# uZed_breakout.net
KiCad netlist of a schematic drawn in Altium Designer
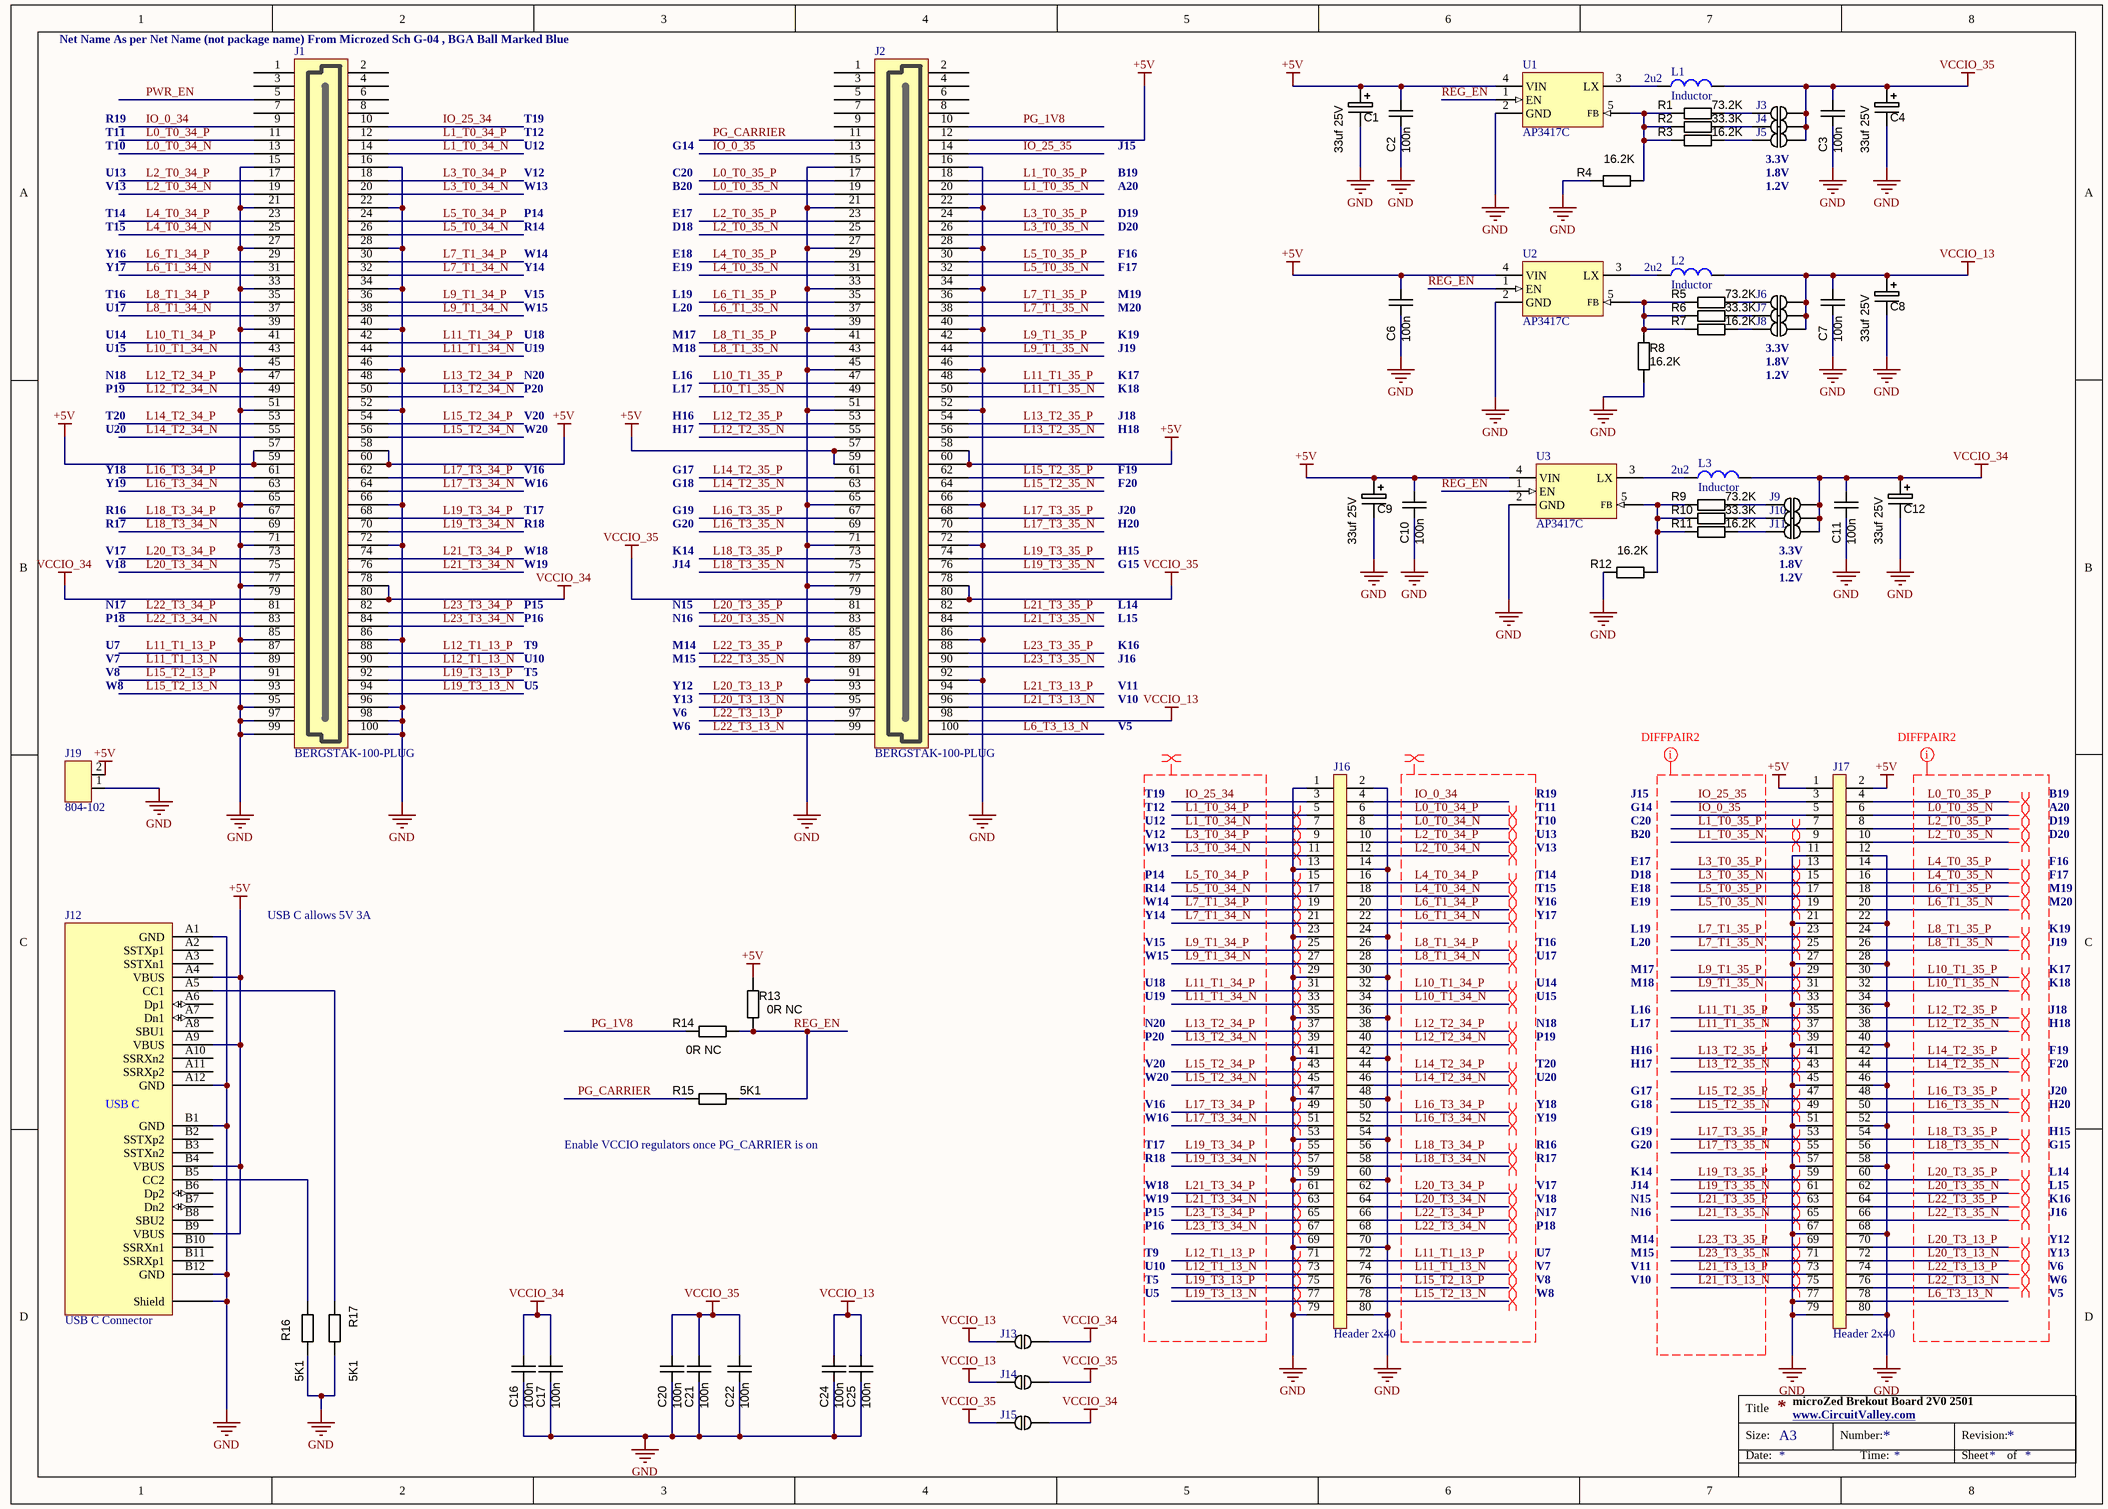
[diagram p0: uZed_breakout.SchDoc]

(export (version "E")
  (design (tool "Eeschema 10.0.6"))
  (components
    (comp (ref "C1")
      (value "33uf 25V")
      (footprint "CAPMP7343X310N")
      (description "Capacitor SMD Tant 330uF 20% 6V3 2917")
      (fields
        (field (name "TOLERANCE") "±20%")
        (field (name "MANUFACTURER PART NUMBER") "T520D337M006ATE015")
      )
      (libsource (lib "PBL - Capacitors") (part "CAPT_330u_2917_6V3"))
    )
    (comp (ref "C2")
      (value "100n")
      (footprint "CAPC1608N")
      (description "Capacitor SMD Cer 10pF 5% 50V NP0 0603")
      (fields (field (name "TOLERANCE") "±5%") (field (name "PART") "C0603X104K5RAC"))
      (libsource (lib "PBL - Capacitors") (part "CAPC_10p_0603_NP0_1%_50V"))
    )
    (comp (ref "C3")
      (value "100n")
      (footprint "CAPC1608N")
      (description "Capacitor SMD Cer 10pF 5% 50V NP0 0603")
      (fields (field (name "TOLERANCE") "±5%") (field (name "PART") "C0603X104K5RAC"))
      (libsource (lib "PBL - Capacitors") (part "CAPC_10p_0603_NP0_1%_50V"))
    )
    (comp (ref "C4")
      (value "33uf 25V")
      (footprint "CAPMP7343X310N")
      (description "Capacitor SMD Tant 330uF 20% 6V3 2917")
      (fields
        (field (name "TOLERANCE") "±20%")
        (field (name "MANUFACTURER PART NUMBER") "T520D337M006ATE015")
      )
      (libsource (lib "PBL - Capacitors") (part "CAPT_330u_2917_6V3"))
    )
    (comp (ref "C6")
      (value "100n")
      (footprint "CAPC1608N")
      (description "Capacitor SMD Cer 10pF 5% 50V NP0 0603")
      (fields (field (name "TOLERANCE") "±5%") (field (name "PART") "C0603X104K5RAC"))
      (libsource (lib "PBL - Capacitors") (part "CAPC_10p_0603_NP0_1%_50V"))
    )
    (comp (ref "C7")
      (value "100n")
      (footprint "CAPC1608N")
      (description "Capacitor SMD Cer 10pF 5% 50V NP0 0603")
      (fields (field (name "TOLERANCE") "±5%") (field (name "PART") "C0603X104K5RAC"))
      (libsource (lib "PBL - Capacitors") (part "CAPC_10p_0603_NP0_1%_50V"))
    )
    (comp (ref "C8")
      (value "33uf 25V")
      (footprint "CAPMP7343X310N")
      (description "Capacitor SMD Tant 330uF 20% 6V3 2917")
      (fields
        (field (name "TOLERANCE") "±20%")
        (field (name "MANUFACTURER PART NUMBER") "T520D337M006ATE015")
      )
      (libsource (lib "PBL - Capacitors") (part "CAPT_330u_2917_6V3"))
    )
    (comp (ref "C9")
      (value "33uf 25V")
      (footprint "CAPMP7343X310N")
      (description "Capacitor SMD Tant 330uF 20% 6V3 2917")
      (fields
        (field (name "TOLERANCE") "±20%")
        (field (name "MANUFACTURER PART NUMBER") "T520D337M006ATE015")
      )
      (libsource (lib "PBL - Capacitors") (part "CAPT_330u_2917_6V3"))
    )
    (comp (ref "C10")
      (value "100n")
      (footprint "CAPC1608N")
      (description "Capacitor SMD Cer 10pF 5% 50V NP0 0603")
      (fields (field (name "TOLERANCE") "±5%") (field (name "PART") "C0603X104K5RAC"))
      (libsource (lib "PBL - Capacitors") (part "CAPC_10p_0603_NP0_1%_50V"))
    )
    (comp (ref "C11")
      (value "100n")
      (footprint "CAPC1608N")
      (description "Capacitor SMD Cer 10pF 5% 50V NP0 0603")
      (fields (field (name "TOLERANCE") "±5%") (field (name "PART") "C0603X104K5RAC"))
      (libsource (lib "PBL - Capacitors") (part "CAPC_10p_0603_NP0_1%_50V"))
    )
    (comp (ref "C12")
      (value "33uf 25V")
      (footprint "CAPMP7343X310N")
      (description "Capacitor SMD Tant 330uF 20% 6V3 2917")
      (fields
        (field (name "TOLERANCE") "±20%")
        (field (name "MANUFACTURER PART NUMBER") "T520D337M006ATE015")
      )
      (libsource (lib "PBL - Capacitors") (part "CAPT_330u_2917_6V3"))
    )
    (comp (ref "C16")
      (value "100n")
      (footprint "CAPC1608N")
      (description "Capacitor SMD Cer 10pF 5% 50V NP0 0603")
      (fields (field (name "TOLERANCE") "±5%") (field (name "PART") "C0603X104K5RAC"))
      (libsource (lib "PBL - Capacitors") (part "CAPC_10p_0603_NP0_1%_50V"))
    )
    (comp (ref "C17")
      (value "100n")
      (footprint "CAPC1608N")
      (description "Capacitor SMD Cer 10pF 5% 50V NP0 0603")
      (fields (field (name "TOLERANCE") "±5%") (field (name "PART") "C0603X104K5RAC"))
      (libsource (lib "PBL - Capacitors") (part "CAPC_10p_0603_NP0_1%_50V"))
    )
    (comp (ref "C20")
      (value "100n")
      (footprint "CAPC1608N")
      (description "Capacitor SMD Cer 10pF 5% 50V NP0 0603")
      (fields (field (name "TOLERANCE") "±5%") (field (name "PART") "C0603X104K5RAC"))
      (libsource (lib "PBL - Capacitors") (part "CAPC_10p_0603_NP0_1%_50V"))
    )
    (comp (ref "C21")
      (value "100n")
      (footprint "CAPC1608N")
      (description "Capacitor SMD Cer 10pF 5% 50V NP0 0603")
      (fields (field (name "TOLERANCE") "±5%") (field (name "PART") "C0603X104K5RAC"))
      (libsource (lib "PBL - Capacitors") (part "CAPC_10p_0603_NP0_1%_50V"))
    )
    (comp (ref "C22")
      (value "100n")
      (footprint "CAPC1608N")
      (description "Capacitor SMD Cer 10pF 5% 50V NP0 0603")
      (fields (field (name "TOLERANCE") "±5%") (field (name "PART") "C0603X104K5RAC"))
      (libsource (lib "PBL - Capacitors") (part "CAPC_10p_0603_NP0_1%_50V"))
    )
    (comp (ref "C24")
      (value "100n")
      (footprint "CAPC1608N")
      (description "Capacitor SMD Cer 10pF 5% 50V NP0 0603")
      (fields (field (name "TOLERANCE") "±5%") (field (name "PART") "C0603X104K5RAC"))
      (libsource (lib "PBL - Capacitors") (part "CAPC_10p_0603_NP0_1%_50V"))
    )
    (comp (ref "C25")
      (value "100n")
      (footprint "CAPC1608N")
      (description "Capacitor SMD Cer 10pF 5% 50V NP0 0603")
      (fields (field (name "TOLERANCE") "±5%") (field (name "PART") "C0603X104K5RAC"))
      (libsource (lib "PBL - Capacitors") (part "CAPC_10p_0603_NP0_1%_50V"))
    )
    (comp (ref "J1")
      (value "BERGSTAK-100-PLUG")
      (footprint "61083-101400LF")
      (libsource (lib "cvlib") (part "BERGSTAK-100-PLUG"))
    )
    (comp (ref "J2")
      (value "BERGSTAK-100-PLUG")
      (footprint "61083-101400LF")
      (libsource (lib "cvlib") (part "BERGSTAK-100-PLUG"))
    )
    (comp (ref "J3")
      (value "SMD Jumper")
      (footprint "SMD_Jumper")
      (libsource (lib "cvlib") (part "SMD_Jumper"))
    )
    (comp (ref "J4")
      (value "SMD Jumper Bridged")
      (footprint "SMD_Jumper_bridge")
      (description "SMD Jumper")
      (libsource (lib "cvlib") (part "SMD_Jumper_Bridged"))
    )
    (comp (ref "J5")
      (value "SMD Jumper")
      (footprint "SMD_Jumper")
      (libsource (lib "cvlib") (part "SMD_Jumper"))
    )
    (comp (ref "J6")
      (value "SMD Jumper")
      (footprint "SMD_Jumper")
      (libsource (lib "cvlib") (part "SMD_Jumper"))
    )
    (comp (ref "J7")
      (value "SMD Jumper Bridged")
      (footprint "SMD_Jumper_bridge")
      (description "SMD Jumper")
      (libsource (lib "cvlib") (part "SMD_Jumper_Bridged"))
    )
    (comp (ref "J8")
      (value "SMD Jumper")
      (footprint "SMD_Jumper")
      (libsource (lib "cvlib") (part "SMD_Jumper"))
    )
    (comp (ref "J9")
      (value "SMD Jumper")
      (footprint "SMD_Jumper")
      (libsource (lib "cvlib") (part "SMD_Jumper"))
    )
    (comp (ref "J10")
      (value "SMD Jumper Bridged")
      (footprint "SMD_Jumper_bridge")
      (description "SMD Jumper")
      (libsource (lib "cvlib") (part "SMD_Jumper_Bridged"))
    )
    (comp (ref "J11")
      (value "SMD Jumper")
      (footprint "SMD_Jumper")
      (libsource (lib "cvlib") (part "SMD_Jumper"))
    )
    (comp (ref "J12")
      (value "USB C Connector")
      (footprint "UT11113-11602-7H")
      (description "USB C connector")
      (libsource (lib "cvlib") (part "USB_C"))
    )
    (comp (ref "J13")
      (value "SMD Jumper")
      (footprint "SMD_Jumper")
      (libsource (lib "cvlib") (part "SMD_Jumper"))
    )
    (comp (ref "J14")
      (value "SMD Jumper")
      (footprint "SMD_Jumper")
      (libsource (lib "cvlib") (part "SMD_Jumper"))
    )
    (comp (ref "J15")
      (value "SMD Jumper")
      (footprint "SMD_Jumper")
      (libsource (lib "cvlib") (part "SMD_Jumper"))
    )
    (comp (ref "J16")
      (value "Header 2x40")
      (footprint "Header_2x40")
      (libsource (lib "cvlib") (part "Header_2x40"))
    )
    (comp (ref "J17")
      (value "Header 2x40")
      (footprint "Header_2x40")
      (libsource (lib "cvlib") (part "Header_2x40"))
    )
    (comp (ref "J19") (value "804-102") (footprint "804-102") (libsource (lib "cvlib") (part "804-102")))
    (comp (ref "L1")
      (value "Inductor")
      (footprint "SFE4018A-2R2M-F-HF")
      (fields (field (name "ALTIUM_VALUE") "2u2"))
      (libsource (lib "cvlib") (part "inductor_smd"))
    )
    (comp (ref "L2")
      (value "Inductor")
      (footprint "SFE4018A-2R2M-F-HF")
      (fields (field (name "ALTIUM_VALUE") "2u2"))
      (libsource (lib "cvlib") (part "inductor_smd"))
    )
    (comp (ref "L3")
      (value "Inductor")
      (footprint "SFE4018A-2R2M-F-HF")
      (fields (field (name "ALTIUM_VALUE") "2u2"))
      (libsource (lib "cvlib") (part "inductor_smd"))
    )
    (comp (ref "R1")
      (value "73.2K")
      (footprint "RESC1608N_ZERO")
      (description "Resistor SMD chip 0.0 Ohm 0.1W 0603")
      (fields (field (name "TOLERANCE") "±5%") (field (name "Comment") "Thick Film"))
      (libsource (lib "PBL - Resistors") (part "RES_0R_0603"))
    )
    (comp (ref "R2")
      (value "33.3K")
      (footprint "RESC1608N_ZERO")
      (description "Resistor SMD chip 0.0 Ohm 0.1W 0603")
      (fields (field (name "TOLERANCE") "±5%") (field (name "Comment") "Thick Film"))
      (libsource (lib "PBL - Resistors") (part "RES_0R_0603"))
    )
    (comp (ref "R3")
      (value "16.2K")
      (footprint "RESC1608N_ZERO")
      (description "Resistor SMD chip 0.0 Ohm 0.1W 0603")
      (fields (field (name "TOLERANCE") "±5%") (field (name "Comment") "Thick Film"))
      (libsource (lib "PBL - Resistors") (part "RES_0R_0603"))
    )
    (comp (ref "R4")
      (value "16.2K")
      (footprint "RESC1608N_ZERO")
      (description "Resistor SMD chip 0.0 Ohm 0.1W 0603")
      (fields (field (name "TOLERANCE") "±5%") (field (name "Comment") "Thick Film"))
      (libsource (lib "PBL - Resistors") (part "RES_0R_0603"))
    )
    (comp (ref "R5")
      (value "73.2K")
      (footprint "RESC1608N_ZERO")
      (description "Resistor SMD chip 0.0 Ohm 0.1W 0603")
      (fields (field (name "TOLERANCE") "±5%") (field (name "Comment") "Thick Film"))
      (libsource (lib "") (part "RES_0R_0603_3"))
    )
    (comp (ref "R6")
      (value "33.3K")
      (footprint "RESC1608N_ZERO")
      (description "Resistor SMD chip 0.0 Ohm 0.1W 0603")
      (fields (field (name "TOLERANCE") "±5%") (field (name "Comment") "Thick Film"))
      (libsource (lib "") (part "RES_0R_0603_3"))
    )
    (comp (ref "R7")
      (value "16.2K")
      (footprint "RESC1608N_ZERO")
      (description "Resistor SMD chip 0.0 Ohm 0.1W 0603")
      (fields (field (name "TOLERANCE") "±5%") (field (name "Comment") "Thick Film"))
      (libsource (lib "") (part "RES_0R_0603_3"))
    )
    (comp (ref "R8")
      (value "16.2K")
      (footprint "RESC1608N_ZERO")
      (description "Resistor SMD chip 0.0 Ohm 0.1W 0603")
      (fields (field (name "TOLERANCE") "±5%") (field (name "Comment") "Thick Film"))
      (libsource (lib "") (part "RES_0R_0603_1"))
    )
    (comp (ref "R9")
      (value "73.2K")
      (footprint "RESC1608N_ZERO")
      (description "Resistor SMD chip 0.0 Ohm 0.1W 0603")
      (fields (field (name "TOLERANCE") "±5%") (field (name "Comment") "Thick Film"))
      (libsource (lib "PBL - Resistors") (part "RES_0R_0603"))
    )
    (comp (ref "R10")
      (value "33.3K")
      (footprint "RESC1608N_ZERO")
      (description "Resistor SMD chip 0.0 Ohm 0.1W 0603")
      (fields (field (name "TOLERANCE") "±5%") (field (name "Comment") "Thick Film"))
      (libsource (lib "PBL - Resistors") (part "RES_0R_0603"))
    )
    (comp (ref "R11")
      (value "16.2K")
      (footprint "RESC1608N_ZERO")
      (description "Resistor SMD chip 0.0 Ohm 0.1W 0603")
      (fields (field (name "TOLERANCE") "±5%") (field (name "Comment") "Thick Film"))
      (libsource (lib "PBL - Resistors") (part "RES_0R_0603"))
    )
    (comp (ref "R12")
      (value "16.2K")
      (footprint "RESC1608N_ZERO")
      (description "Resistor SMD chip 0.0 Ohm 0.1W 0603")
      (fields (field (name "TOLERANCE") "±5%") (field (name "Comment") "Thick Film"))
      (libsource (lib "PBL - Resistors") (part "RES_0R_0603"))
    )
    (comp (ref "R13")
      (value "0R NC")
      (footprint "RESC1608N_ZERO")
      (description "Resistor SMD chip 0.0 Ohm 0.1W 0603")
      (fields (field (name "TOLERANCE") "±5%") (field (name "Comment") "Thick Film"))
      (libsource (lib "") (part "RES_0R_0603_2"))
    )
    (comp (ref "R14")
      (value "0R NC")
      (footprint "RESC1608N_ZERO")
      (description "Resistor SMD chip 0.0 Ohm 0.1W 0603")
      (fields (field (name "TOLERANCE") "±5%") (field (name "Comment") "Thick Film"))
      (libsource (lib "PBL - Resistors") (part "RES_0R_0603"))
    )
    (comp (ref "R15")
      (value "5K1")
      (footprint "RESC1608N_ZERO")
      (description "Resistor SMD chip 0.0 Ohm 0.1W 0603")
      (fields (field (name "TOLERANCE") "±5%") (field (name "Comment") "Thick Film"))
      (libsource (lib "PBL - Resistors") (part "RES_0R_0603"))
    )
    (comp (ref "R16")
      (value "5K1")
      (footprint "RESC1608N_ZERO")
      (description "Resistor SMD chip 0.0 Ohm 0.1W 0603")
      (fields (field (name "TOLERANCE") "±5%") (field (name "Comment") "Thick Film"))
      (libsource (lib "") (part "RES_0R_0603_2"))
    )
    (comp (ref "R17")
      (value "5K1")
      (footprint "RESC1608N_ZERO")
      (description "Resistor SMD chip 0.0 Ohm 0.1W 0603")
      (fields (field (name "TOLERANCE") "±5%") (field (name "Comment") "Thick Film"))
      (libsource (lib "") (part "RES_0R_0603_2"))
    )
    (comp (ref "U1") (value "AP3417C") (footprint "SOT23-5") (libsource (lib "cvlib") (part "AP3417C")))
    (comp (ref "U2") (value "AP3417C") (footprint "SOT23-5") (libsource (lib "cvlib") (part "AP3417C")))
    (comp (ref "U3") (value "AP3417C") (footprint "SOT23-5") (libsource (lib "cvlib") (part "AP3417C")))
  )
  (nets
    (net (code "1") (name "+5V") (class "Default")
      (node (ref "C1") (pin "1") (pintype "passive"))
      (node (ref "C10") (pin "2") (pintype "passive"))
      (node (ref "C2") (pin "2") (pintype "passive"))
      (node (ref "C6") (pin "2") (pintype "passive"))
      (node (ref "C9") (pin "1") (pintype "passive"))
      (node (ref "J1") (pin "57") (pinfunction "57_57") (pintype "passive"))
      (node (ref "J1") (pin "58") (pinfunction "58_58") (pintype "passive"))
      (node (ref "J1") (pin "59") (pinfunction "59_59") (pintype "passive"))
      (node (ref "J1") (pin "60") (pinfunction "60_60") (pintype "passive"))
      (node (ref "J12") (pin "A4") (pinfunction "VBUS_A4") (pintype "power_in"))
      (node (ref "J12") (pin "A9") (pinfunction "VBUS_A9") (pintype "power_in"))
      (node (ref "J12") (pin "B4") (pinfunction "VBUS_B4") (pintype "power_in"))
      (node (ref "J12") (pin "B9") (pinfunction "VBUS_B9") (pintype "power_in"))
      (node (ref "J17") (pin "1") (pinfunction "1_1") (pintype "passive"))
      (node (ref "J17") (pin "2") (pinfunction "2_2") (pintype "passive"))
      (node (ref "J19") (pin "2") (pinfunction "PW_2") (pintype "passive"))
      (node (ref "J2") (pin "12") (pinfunction "12_12") (pintype "passive"))
      (node (ref "J2") (pin "57") (pinfunction "57_57") (pintype "passive"))
      (node (ref "J2") (pin "58") (pinfunction "58_58") (pintype "passive"))
      (node (ref "J2") (pin "59") (pinfunction "59_59") (pintype "passive"))
      (node (ref "J2") (pin "60") (pinfunction "60_60") (pintype "passive"))
      (node (ref "R13") (pin "1") (pinfunction "1_1") (pintype "passive"))
      (node (ref "U1") (pin "4") (pinfunction "VIN_4") (pintype "power_in"))
      (node (ref "U2") (pin "4") (pinfunction "VIN_4") (pintype "power_in"))
      (node (ref "U3") (pin "4") (pinfunction "VIN_4") (pintype "power_in"))
    )
    (net (code "2") (name "/IO_0_34") (class "Default")
      (node (ref "J1") (pin "9") (pinfunction "9_9") (pintype "passive"))
      (node (ref "J16") (pin "4") (pinfunction "4_4") (pintype "passive"))
    )
    (net (code "3") (name "/IO_0_35") (class "Default")
      (node (ref "J17") (pin "5") (pinfunction "5_5") (pintype "passive"))
      (node (ref "J2") (pin "13") (pinfunction "13_13") (pintype "passive"))
    )
    (net (code "4") (name "/IO_25_34") (class "Default")
      (node (ref "J1") (pin "10") (pinfunction "10_10") (pintype "passive"))
      (node (ref "J16") (pin "3") (pinfunction "3_3") (pintype "passive"))
    )
    (net (code "5") (name "/IO_25_35") (class "Default")
      (node (ref "J17") (pin "3") (pinfunction "3_3") (pintype "passive"))
      (node (ref "J2") (pin "14") (pinfunction "14_14") (pintype "passive"))
    )
    (net (code "6") (name "/L0_T0_34_N") (class "Default")
      (node (ref "J1") (pin "13") (pinfunction "13_13") (pintype "passive"))
      (node (ref "J16") (pin "8") (pinfunction "8_8") (pintype "passive"))
    )
    (net (code "7") (name "/L0_T0_34_P") (class "Default")
      (node (ref "J1") (pin "11") (pinfunction "11_11") (pintype "passive"))
      (node (ref "J16") (pin "6") (pinfunction "6_6") (pintype "passive"))
    )
    (net (code "8") (name "/L0_T0_35_N") (class "Default")
      (node (ref "J17") (pin "6") (pinfunction "6_6") (pintype "passive"))
      (node (ref "J2") (pin "19") (pinfunction "19_19") (pintype "passive"))
    )
    (net (code "9") (name "/L0_T0_35_P") (class "Default")
      (node (ref "J17") (pin "4") (pinfunction "4_4") (pintype "passive"))
      (node (ref "J2") (pin "17") (pinfunction "17_17") (pintype "passive"))
    )
    (net (code "10") (name "/L1_T0_34_N") (class "Default")
      (node (ref "J1") (pin "14") (pinfunction "14_14") (pintype "passive"))
      (node (ref "J16") (pin "7") (pinfunction "7_7") (pintype "passive"))
    )
    (net (code "11") (name "/L1_T0_34_P") (class "Default")
      (node (ref "J1") (pin "12") (pinfunction "12_12") (pintype "passive"))
      (node (ref "J16") (pin "5") (pinfunction "5_5") (pintype "passive"))
    )
    (net (code "12") (name "/L1_T0_35_N") (class "Default")
      (node (ref "J17") (pin "9") (pinfunction "9_9") (pintype "passive"))
      (node (ref "J2") (pin "20") (pinfunction "20_20") (pintype "passive"))
    )
    (net (code "13") (name "/L1_T0_35_P") (class "Default")
      (node (ref "J17") (pin "7") (pinfunction "7_7") (pintype "passive"))
      (node (ref "J2") (pin "18") (pinfunction "18_18") (pintype "passive"))
    )
    (net (code "14") (name "/L2_T0_34_N") (class "Default")
      (node (ref "J1") (pin "19") (pinfunction "19_19") (pintype "passive"))
      (node (ref "J16") (pin "12") (pinfunction "12_12") (pintype "passive"))
    )
    (net (code "15") (name "/L2_T0_34_P") (class "Default")
      (node (ref "J1") (pin "17") (pinfunction "17_17") (pintype "passive"))
      (node (ref "J16") (pin "10") (pinfunction "10_10") (pintype "passive"))
    )
    (net (code "16") (name "/L2_T0_35_N") (class "Default")
      (node (ref "J17") (pin "10") (pinfunction "10_10") (pintype "passive"))
      (node (ref "J2") (pin "25") (pinfunction "25_25") (pintype "passive"))
    )
    (net (code "17") (name "/L2_T0_35_P") (class "Default")
      (node (ref "J17") (pin "8") (pinfunction "8_8") (pintype "passive"))
      (node (ref "J2") (pin "23") (pinfunction "23_23") (pintype "passive"))
    )
    (net (code "18") (name "/L3_T0_34_N") (class "Default")
      (node (ref "J1") (pin "20") (pinfunction "20_20") (pintype "passive"))
      (node (ref "J16") (pin "11") (pinfunction "11_11") (pintype "passive"))
    )
    (net (code "19") (name "/L3_T0_34_P") (class "Default")
      (node (ref "J1") (pin "18") (pinfunction "18_18") (pintype "passive"))
      (node (ref "J16") (pin "9") (pinfunction "9_9") (pintype "passive"))
    )
    (net (code "20") (name "/L3_T0_35_N") (class "Default")
      (node (ref "J17") (pin "15") (pinfunction "15_15") (pintype "passive"))
      (node (ref "J2") (pin "26") (pinfunction "26_26") (pintype "passive"))
    )
    (net (code "21") (name "/L3_T0_35_P") (class "Default")
      (node (ref "J17") (pin "13") (pinfunction "13_13") (pintype "passive"))
      (node (ref "J2") (pin "24") (pinfunction "24_24") (pintype "passive"))
    )
    (net (code "22") (name "/L4_T0_34_N") (class "Default")
      (node (ref "J1") (pin "25") (pinfunction "25_25") (pintype "passive"))
      (node (ref "J16") (pin "18") (pinfunction "18_18") (pintype "passive"))
    )
    (net (code "23") (name "/L4_T0_34_P") (class "Default")
      (node (ref "J1") (pin "23") (pinfunction "23_23") (pintype "passive"))
      (node (ref "J16") (pin "16") (pinfunction "16_16") (pintype "passive"))
    )
    (net (code "24") (name "/L4_T0_35_N") (class "Default")
      (node (ref "J17") (pin "16") (pinfunction "16_16") (pintype "passive"))
      (node (ref "J2") (pin "31") (pinfunction "31_31") (pintype "passive"))
    )
    (net (code "25") (name "/L4_T0_35_P") (class "Default")
      (node (ref "J17") (pin "14") (pinfunction "14_14") (pintype "passive"))
      (node (ref "J2") (pin "29") (pinfunction "29_29") (pintype "passive"))
    )
    (net (code "26") (name "/L5_T0_34_N") (class "Default")
      (node (ref "J1") (pin "26") (pinfunction "26_26") (pintype "passive"))
      (node (ref "J16") (pin "17") (pinfunction "17_17") (pintype "passive"))
    )
    (net (code "27") (name "/L5_T0_34_P") (class "Default")
      (node (ref "J1") (pin "24") (pinfunction "24_24") (pintype "passive"))
      (node (ref "J16") (pin "15") (pinfunction "15_15") (pintype "passive"))
    )
    (net (code "28") (name "/L5_T0_35_N") (class "Default")
      (node (ref "J17") (pin "19") (pinfunction "19_19") (pintype "passive"))
      (node (ref "J2") (pin "32") (pinfunction "32_32") (pintype "passive"))
    )
    (net (code "29") (name "/L5_T0_35_P") (class "Default")
      (node (ref "J17") (pin "17") (pinfunction "17_17") (pintype "passive"))
      (node (ref "J2") (pin "30") (pinfunction "30_30") (pintype "passive"))
    )
    (net (code "30") (name "/L6_T1_34_N") (class "Default")
      (node (ref "J1") (pin "31") (pinfunction "31_31") (pintype "passive"))
      (node (ref "J16") (pin "22") (pinfunction "22_22") (pintype "passive"))
    )
    (net (code "31") (name "/L6_T1_34_P") (class "Default")
      (node (ref "J1") (pin "29") (pinfunction "29_29") (pintype "passive"))
      (node (ref "J16") (pin "20") (pinfunction "20_20") (pintype "passive"))
    )
    (net (code "32") (name "/L6_T1_35_N") (class "Default")
      (node (ref "J17") (pin "20") (pinfunction "20_20") (pintype "passive"))
      (node (ref "J2") (pin "37") (pinfunction "37_37") (pintype "passive"))
    )
    (net (code "33") (name "/L6_T1_35_P") (class "Default")
      (node (ref "J17") (pin "18") (pinfunction "18_18") (pintype "passive"))
      (node (ref "J2") (pin "35") (pinfunction "35_35") (pintype "passive"))
    )
    (net (code "34") (name "/L6_T3_13_N") (class "Default")
      (node (ref "J17") (pin "78") (pinfunction "78_78") (pintype "passive"))
      (node (ref "J2") (pin "100") (pinfunction "100_100") (pintype "passive"))
    )
    (net (code "35") (name "/L7_T1_34_N") (class "Default")
      (node (ref "J1") (pin "32") (pinfunction "32_32") (pintype "passive"))
      (node (ref "J16") (pin "21") (pinfunction "21_21") (pintype "passive"))
    )
    (net (code "36") (name "/L7_T1_34_P") (class "Default")
      (node (ref "J1") (pin "30") (pinfunction "30_30") (pintype "passive"))
      (node (ref "J16") (pin "19") (pinfunction "19_19") (pintype "passive"))
    )
    (net (code "37") (name "/L7_T1_35_N") (class "Default")
      (node (ref "J17") (pin "25") (pinfunction "25_25") (pintype "passive"))
      (node (ref "J2") (pin "38") (pinfunction "38_38") (pintype "passive"))
    )
    (net (code "38") (name "/L7_T1_35_P") (class "Default")
      (node (ref "J17") (pin "23") (pinfunction "23_23") (pintype "passive"))
      (node (ref "J2") (pin "36") (pinfunction "36_36") (pintype "passive"))
    )
    (net (code "39") (name "/L8_T1_34_N") (class "Default")
      (node (ref "J1") (pin "37") (pinfunction "37_37") (pintype "passive"))
      (node (ref "J16") (pin "28") (pinfunction "28_28") (pintype "passive"))
    )
    (net (code "40") (name "/L8_T1_34_P") (class "Default")
      (node (ref "J1") (pin "35") (pinfunction "35_35") (pintype "passive"))
      (node (ref "J16") (pin "26") (pinfunction "26_26") (pintype "passive"))
    )
    (net (code "41") (name "/L8_T1_35_N") (class "Default")
      (node (ref "J17") (pin "26") (pinfunction "26_26") (pintype "passive"))
      (node (ref "J2") (pin "43") (pinfunction "43_43") (pintype "passive"))
    )
    (net (code "42") (name "/L8_T1_35_P") (class "Default")
      (node (ref "J17") (pin "24") (pinfunction "24_24") (pintype "passive"))
      (node (ref "J2") (pin "41") (pinfunction "41_41") (pintype "passive"))
    )
    (net (code "43") (name "/L9_T1_34_N") (class "Default")
      (node (ref "J1") (pin "38") (pinfunction "38_38") (pintype "passive"))
      (node (ref "J16") (pin "27") (pinfunction "27_27") (pintype "passive"))
    )
    (net (code "44") (name "/L9_T1_34_P") (class "Default")
      (node (ref "J1") (pin "36") (pinfunction "36_36") (pintype "passive"))
      (node (ref "J16") (pin "25") (pinfunction "25_25") (pintype "passive"))
    )
    (net (code "45") (name "/L9_T1_35_N") (class "Default")
      (node (ref "J17") (pin "31") (pinfunction "31_31") (pintype "passive"))
      (node (ref "J2") (pin "44") (pinfunction "44_44") (pintype "passive"))
    )
    (net (code "46") (name "/L9_T1_35_P") (class "Default")
      (node (ref "J17") (pin "29") (pinfunction "29_29") (pintype "passive"))
      (node (ref "J2") (pin "42") (pinfunction "42_42") (pintype "passive"))
    )
    (net (code "47") (name "/L10_T1_34_N") (class "Default")
      (node (ref "J1") (pin "43") (pinfunction "43_43") (pintype "passive"))
      (node (ref "J16") (pin "34") (pinfunction "34_34") (pintype "passive"))
    )
    (net (code "48") (name "/L10_T1_34_P") (class "Default")
      (node (ref "J1") (pin "41") (pinfunction "41_41") (pintype "passive"))
      (node (ref "J16") (pin "32") (pinfunction "32_32") (pintype "passive"))
    )
    (net (code "49") (name "/L10_T1_35_N") (class "Default")
      (node (ref "J17") (pin "32") (pinfunction "32_32") (pintype "passive"))
      (node (ref "J2") (pin "49") (pinfunction "49_49") (pintype "passive"))
    )
    (net (code "50") (name "/L10_T1_35_P") (class "Default")
      (node (ref "J17") (pin "30") (pinfunction "30_30") (pintype "passive"))
      (node (ref "J2") (pin "47") (pinfunction "47_47") (pintype "passive"))
    )
    (net (code "51") (name "/L11_T1_13_N") (class "Default")
      (node (ref "J1") (pin "89") (pinfunction "89_89") (pintype "passive"))
      (node (ref "J16") (pin "74") (pinfunction "74_74") (pintype "passive"))
    )
    (net (code "52") (name "/L11_T1_13_P") (class "Default")
      (node (ref "J1") (pin "87") (pinfunction "87_87") (pintype "passive"))
      (node (ref "J16") (pin "72") (pinfunction "72_72") (pintype "passive"))
    )
    (net (code "53") (name "/L11_T1_34_N") (class "Default")
      (node (ref "J1") (pin "44") (pinfunction "44_44") (pintype "passive"))
      (node (ref "J16") (pin "33") (pinfunction "33_33") (pintype "passive"))
    )
    (net (code "54") (name "/L11_T1_34_P") (class "Default")
      (node (ref "J1") (pin "42") (pinfunction "42_42") (pintype "passive"))
      (node (ref "J16") (pin "31") (pinfunction "31_31") (pintype "passive"))
    )
    (net (code "55") (name "/L11_T1_35_N") (class "Default")
      (node (ref "J17") (pin "37") (pinfunction "37_37") (pintype "passive"))
      (node (ref "J2") (pin "50") (pinfunction "50_50") (pintype "passive"))
    )
    (net (code "56") (name "/L11_T1_35_P") (class "Default")
      (node (ref "J17") (pin "35") (pinfunction "35_35") (pintype "passive"))
      (node (ref "J2") (pin "48") (pinfunction "48_48") (pintype "passive"))
    )
    (net (code "57") (name "/L12_T1_13_N") (class "Default")
      (node (ref "J1") (pin "90") (pinfunction "90_90") (pintype "passive"))
      (node (ref "J16") (pin "73") (pinfunction "73_73") (pintype "passive"))
    )
    (net (code "58") (name "/L12_T1_13_P") (class "Default")
      (node (ref "J1") (pin "88") (pinfunction "88_88") (pintype "passive"))
      (node (ref "J16") (pin "71") (pinfunction "71_71") (pintype "passive"))
    )
    (net (code "59") (name "/L12_T2_34_N") (class "Default")
      (node (ref "J1") (pin "49") (pinfunction "49_49") (pintype "passive"))
      (node (ref "J16") (pin "40") (pinfunction "40_40") (pintype "passive"))
    )
    (net (code "60") (name "/L12_T2_34_P") (class "Default")
      (node (ref "J1") (pin "47") (pinfunction "47_47") (pintype "passive"))
      (node (ref "J16") (pin "38") (pinfunction "38_38") (pintype "passive"))
    )
    (net (code "61") (name "/L12_T2_35_N") (class "Default")
      (node (ref "J17") (pin "38") (pinfunction "38_38") (pintype "passive"))
      (node (ref "J2") (pin "55") (pinfunction "55_55") (pintype "passive"))
    )
    (net (code "62") (name "/L12_T2_35_P") (class "Default")
      (node (ref "J17") (pin "36") (pinfunction "36_36") (pintype "passive"))
      (node (ref "J2") (pin "53") (pinfunction "53_53") (pintype "passive"))
    )
    (net (code "63") (name "/L13_T2_34_N") (class "Default")
      (node (ref "J1") (pin "50") (pinfunction "50_50") (pintype "passive"))
      (node (ref "J16") (pin "39") (pinfunction "39_39") (pintype "passive"))
    )
    (net (code "64") (name "/L13_T2_34_P") (class "Default")
      (node (ref "J1") (pin "48") (pinfunction "48_48") (pintype "passive"))
      (node (ref "J16") (pin "37") (pinfunction "37_37") (pintype "passive"))
    )
    (net (code "65") (name "/L13_T2_35_N") (class "Default")
      (node (ref "J17") (pin "43") (pinfunction "43_43") (pintype "passive"))
      (node (ref "J2") (pin "56") (pinfunction "56_56") (pintype "passive"))
    )
    (net (code "66") (name "/L13_T2_35_P") (class "Default")
      (node (ref "J17") (pin "41") (pinfunction "41_41") (pintype "passive"))
      (node (ref "J2") (pin "54") (pinfunction "54_54") (pintype "passive"))
    )
    (net (code "67") (name "/L14_T2_34_N") (class "Default")
      (node (ref "J1") (pin "55") (pinfunction "55_55") (pintype "passive"))
      (node (ref "J16") (pin "46") (pinfunction "46_46") (pintype "passive"))
    )
    (net (code "68") (name "/L14_T2_34_P") (class "Default")
      (node (ref "J1") (pin "53") (pinfunction "53_53") (pintype "passive"))
      (node (ref "J16") (pin "44") (pinfunction "44_44") (pintype "passive"))
    )
    (net (code "69") (name "/L14_T2_35_N") (class "Default")
      (node (ref "J17") (pin "44") (pinfunction "44_44") (pintype "passive"))
      (node (ref "J2") (pin "63") (pinfunction "63_63") (pintype "passive"))
    )
    (net (code "70") (name "/L14_T2_35_P") (class "Default")
      (node (ref "J17") (pin "42") (pinfunction "42_42") (pintype "passive"))
      (node (ref "J2") (pin "61") (pinfunction "61_61") (pintype "passive"))
    )
    (net (code "71") (name "/L15_T2_13_N") (class "Default")
      (node (ref "J1") (pin "93") (pinfunction "93_93") (pintype "passive"))
      (node (ref "J16") (pin "78") (pinfunction "78_78") (pintype "passive"))
    )
    (net (code "72") (name "/L15_T2_13_P") (class "Default")
      (node (ref "J1") (pin "91") (pinfunction "91_91") (pintype "passive"))
      (node (ref "J16") (pin "76") (pinfunction "76_76") (pintype "passive"))
    )
    (net (code "73") (name "/L15_T2_34_N") (class "Default")
      (node (ref "J1") (pin "56") (pinfunction "56_56") (pintype "passive"))
      (node (ref "J16") (pin "45") (pinfunction "45_45") (pintype "passive"))
    )
    (net (code "74") (name "/L15_T2_34_P") (class "Default")
      (node (ref "J1") (pin "54") (pinfunction "54_54") (pintype "passive"))
      (node (ref "J16") (pin "43") (pinfunction "43_43") (pintype "passive"))
    )
    (net (code "75") (name "/L15_T2_35_N") (class "Default")
      (node (ref "J17") (pin "49") (pinfunction "49_49") (pintype "passive"))
      (node (ref "J2") (pin "64") (pinfunction "64_64") (pintype "passive"))
    )
    (net (code "76") (name "/L15_T2_35_P") (class "Default")
      (node (ref "J17") (pin "47") (pinfunction "47_47") (pintype "passive"))
      (node (ref "J2") (pin "62") (pinfunction "62_62") (pintype "passive"))
    )
    (net (code "77") (name "/L16_T3_34_N") (class "Default")
      (node (ref "J1") (pin "63") (pinfunction "63_63") (pintype "passive"))
      (node (ref "J16") (pin "52") (pinfunction "52_52") (pintype "passive"))
    )
    (net (code "78") (name "/L16_T3_34_P") (class "Default")
      (node (ref "J1") (pin "61") (pinfunction "61_61") (pintype "passive"))
      (node (ref "J16") (pin "50") (pinfunction "50_50") (pintype "passive"))
    )
    (net (code "79") (name "/L16_T3_35_N") (class "Default")
      (node (ref "J17") (pin "50") (pinfunction "50_50") (pintype "passive"))
      (node (ref "J2") (pin "69") (pinfunction "69_69") (pintype "passive"))
    )
    (net (code "80") (name "/L16_T3_35_P") (class "Default")
      (node (ref "J17") (pin "48") (pinfunction "48_48") (pintype "passive"))
      (node (ref "J2") (pin "67") (pinfunction "67_67") (pintype "passive"))
    )
    (net (code "81") (name "/L17_T3_34_N") (class "Default")
      (node (ref "J1") (pin "64") (pinfunction "64_64") (pintype "passive"))
      (node (ref "J16") (pin "51") (pinfunction "51_51") (pintype "passive"))
    )
    (net (code "82") (name "/L17_T3_34_P") (class "Default")
      (node (ref "J1") (pin "62") (pinfunction "62_62") (pintype "passive"))
      (node (ref "J16") (pin "49") (pinfunction "49_49") (pintype "passive"))
    )
    (net (code "83") (name "/L17_T3_35_N") (class "Default")
      (node (ref "J17") (pin "55") (pinfunction "55_55") (pintype "passive"))
      (node (ref "J2") (pin "70") (pinfunction "70_70") (pintype "passive"))
    )
    (net (code "84") (name "/L17_T3_35_P") (class "Default")
      (node (ref "J17") (pin "53") (pinfunction "53_53") (pintype "passive"))
      (node (ref "J2") (pin "68") (pinfunction "68_68") (pintype "passive"))
    )
    (net (code "85") (name "/L18_T3_34_N") (class "Default")
      (node (ref "J1") (pin "69") (pinfunction "69_69") (pintype "passive"))
      (node (ref "J16") (pin "58") (pinfunction "58_58") (pintype "passive"))
    )
    (net (code "86") (name "/L18_T3_34_P") (class "Default")
      (node (ref "J1") (pin "67") (pinfunction "67_67") (pintype "passive"))
      (node (ref "J16") (pin "56") (pinfunction "56_56") (pintype "passive"))
    )
    (net (code "87") (name "/L18_T3_35_N") (class "Default")
      (node (ref "J17") (pin "56") (pinfunction "56_56") (pintype "passive"))
      (node (ref "J2") (pin "75") (pinfunction "75_75") (pintype "passive"))
    )
    (net (code "88") (name "/L18_T3_35_P") (class "Default")
      (node (ref "J17") (pin "54") (pinfunction "54_54") (pintype "passive"))
      (node (ref "J2") (pin "73") (pinfunction "73_73") (pintype "passive"))
    )
    (net (code "89") (name "/L19_T3_13_N") (class "Default")
      (node (ref "J1") (pin "94") (pinfunction "94_94") (pintype "passive"))
      (node (ref "J16") (pin "77") (pinfunction "77_77") (pintype "passive"))
    )
    (net (code "90") (name "/L19_T3_13_P") (class "Default")
      (node (ref "J1") (pin "92") (pinfunction "92_92") (pintype "passive"))
      (node (ref "J16") (pin "75") (pinfunction "75_75") (pintype "passive"))
    )
    (net (code "91") (name "/L19_T3_34_N") (class "Default")
      (node (ref "J1") (pin "70") (pinfunction "70_70") (pintype "passive"))
      (node (ref "J16") (pin "57") (pinfunction "57_57") (pintype "passive"))
    )
    (net (code "92") (name "/L19_T3_34_P") (class "Default")
      (node (ref "J1") (pin "68") (pinfunction "68_68") (pintype "passive"))
      (node (ref "J16") (pin "55") (pinfunction "55_55") (pintype "passive"))
    )
    (net (code "93") (name "/L19_T3_35_N") (class "Default")
      (node (ref "J17") (pin "61") (pinfunction "61_61") (pintype "passive"))
      (node (ref "J2") (pin "76") (pinfunction "76_76") (pintype "passive"))
    )
    (net (code "94") (name "/L19_T3_35_P") (class "Default")
      (node (ref "J17") (pin "59") (pinfunction "59_59") (pintype "passive"))
      (node (ref "J2") (pin "74") (pinfunction "74_74") (pintype "passive"))
    )
    (net (code "95") (name "/L20_T3_13_N") (class "Default")
      (node (ref "J17") (pin "72") (pinfunction "72_72") (pintype "passive"))
      (node (ref "J2") (pin "95") (pinfunction "95_95") (pintype "passive"))
    )
    (net (code "96") (name "/L20_T3_13_P") (class "Default")
      (node (ref "J17") (pin "70") (pinfunction "70_70") (pintype "passive"))
      (node (ref "J2") (pin "93") (pinfunction "93_93") (pintype "passive"))
    )
    (net (code "97") (name "/L20_T3_34_N") (class "Default")
      (node (ref "J1") (pin "75") (pinfunction "75_75") (pintype "passive"))
      (node (ref "J16") (pin "64") (pinfunction "64_64") (pintype "passive"))
    )
    (net (code "98") (name "/L20_T3_34_P") (class "Default")
      (node (ref "J1") (pin "73") (pinfunction "73_73") (pintype "passive"))
      (node (ref "J16") (pin "62") (pinfunction "62_62") (pintype "passive"))
    )
    (net (code "99") (name "/L20_T3_35_N") (class "Default")
      (node (ref "J17") (pin "62") (pinfunction "62_62") (pintype "passive"))
      (node (ref "J2") (pin "83") (pinfunction "83_83") (pintype "passive"))
    )
    (net (code "100") (name "/L20_T3_35_P") (class "Default")
      (node (ref "J17") (pin "60") (pinfunction "60_60") (pintype "passive"))
      (node (ref "J2") (pin "81") (pinfunction "81_81") (pintype "passive"))
    )
    (net (code "101") (name "/L21_T3_13_N") (class "Default")
      (node (ref "J17") (pin "75") (pinfunction "75_75") (pintype "passive"))
      (node (ref "J2") (pin "96") (pinfunction "96_96") (pintype "passive"))
    )
    (net (code "102") (name "/L21_T3_13_P") (class "Default")
      (node (ref "J17") (pin "73") (pinfunction "73_73") (pintype "passive"))
      (node (ref "J2") (pin "94") (pinfunction "94_94") (pintype "passive"))
    )
    (net (code "103") (name "/L21_T3_34_N") (class "Default")
      (node (ref "J1") (pin "76") (pinfunction "76_76") (pintype "passive"))
      (node (ref "J16") (pin "63") (pinfunction "63_63") (pintype "passive"))
    )
    (net (code "104") (name "/L21_T3_34_P") (class "Default")
      (node (ref "J1") (pin "74") (pinfunction "74_74") (pintype "passive"))
      (node (ref "J16") (pin "61") (pinfunction "61_61") (pintype "passive"))
    )
    (net (code "105") (name "/L21_T3_35_N") (class "Default")
      (node (ref "J17") (pin "65") (pinfunction "65_65") (pintype "passive"))
      (node (ref "J2") (pin "84") (pinfunction "84_84") (pintype "passive"))
    )
    (net (code "106") (name "/L21_T3_35_P") (class "Default")
      (node (ref "J17") (pin "63") (pinfunction "63_63") (pintype "passive"))
      (node (ref "J2") (pin "82") (pinfunction "82_82") (pintype "passive"))
    )
    (net (code "107") (name "/L22_T3_13_N") (class "Default")
      (node (ref "J17") (pin "76") (pinfunction "76_76") (pintype "passive"))
      (node (ref "J2") (pin "99") (pinfunction "99_99") (pintype "passive"))
    )
    (net (code "108") (name "/L22_T3_13_P") (class "Default")
      (node (ref "J17") (pin "74") (pinfunction "74_74") (pintype "passive"))
      (node (ref "J2") (pin "97") (pinfunction "97_97") (pintype "passive"))
    )
    (net (code "109") (name "/L22_T3_34_N") (class "Default")
      (node (ref "J1") (pin "83") (pinfunction "83_83") (pintype "passive"))
      (node (ref "J16") (pin "68") (pinfunction "68_68") (pintype "passive"))
    )
    (net (code "110") (name "/L22_T3_34_P") (class "Default")
      (node (ref "J1") (pin "81") (pinfunction "81_81") (pintype "passive"))
      (node (ref "J16") (pin "66") (pinfunction "66_66") (pintype "passive"))
    )
    (net (code "111") (name "/L22_T3_35_N") (class "Default")
      (node (ref "J17") (pin "66") (pinfunction "66_66") (pintype "passive"))
      (node (ref "J2") (pin "89") (pinfunction "89_89") (pintype "passive"))
    )
    (net (code "112") (name "/L22_T3_35_P") (class "Default")
      (node (ref "J17") (pin "64") (pinfunction "64_64") (pintype "passive"))
      (node (ref "J2") (pin "87") (pinfunction "87_87") (pintype "passive"))
    )
    (net (code "113") (name "/L23_T3_34_N") (class "Default")
      (node (ref "J1") (pin "84") (pinfunction "84_84") (pintype "passive"))
      (node (ref "J16") (pin "67") (pinfunction "67_67") (pintype "passive"))
    )
    (net (code "114") (name "/L23_T3_34_P") (class "Default")
      (node (ref "J1") (pin "82") (pinfunction "82_82") (pintype "passive"))
      (node (ref "J16") (pin "65") (pinfunction "65_65") (pintype "passive"))
    )
    (net (code "115") (name "/L23_T3_35_N") (class "Default")
      (node (ref "J17") (pin "71") (pinfunction "71_71") (pintype "passive"))
      (node (ref "J2") (pin "90") (pinfunction "90_90") (pintype "passive"))
    )
    (net (code "116") (name "/L23_T3_35_P") (class "Default")
      (node (ref "J17") (pin "69") (pinfunction "69_69") (pintype "passive"))
      (node (ref "J2") (pin "88") (pinfunction "88_88") (pintype "passive"))
    )
    (net (code "117") (name "/PG_1V8") (class "Default")
      (node (ref "J2") (pin "10") (pinfunction "10_10") (pintype "passive"))
      (node (ref "R14") (pin "2") (pinfunction "2_2") (pintype "passive"))
    )
    (net (code "118") (name "/PG_CARRIER") (class "Default")
      (node (ref "J2") (pin "11") (pinfunction "11_11") (pintype "passive"))
      (node (ref "R15") (pin "2") (pinfunction "2_2") (pintype "passive"))
    )
    (net (code "119") (name "/PWR_EN") (class "Default")
      (node (ref "J1") (pin "5") (pinfunction "5_5") (pintype "passive"))
    )
    (net (code "120") (name "/REG_EN") (class "Default")
      (node (ref "R13") (pin "2") (pinfunction "2_2") (pintype "passive"))
      (node (ref "R14") (pin "1") (pinfunction "1_1") (pintype "passive"))
      (node (ref "R15") (pin "1") (pinfunction "1_1") (pintype "passive"))
      (node (ref "U1") (pin "1") (pinfunction "EN_1") (pintype "input"))
      (node (ref "U2") (pin "1") (pinfunction "EN_1") (pintype "input"))
      (node (ref "U3") (pin "1") (pinfunction "EN_1") (pintype "input"))
    )
    (net (code "121") (name "GND") (class "Default")
      (node (ref "C1") (pin "2") (pintype "passive"))
      (node (ref "C10") (pin "1") (pintype "passive"))
      (node (ref "C11") (pin "1") (pintype "passive"))
      (node (ref "C12") (pin "2") (pintype "passive"))
      (node (ref "C16") (pin "1") (pintype "passive"))
      (node (ref "C17") (pin "1") (pintype "passive"))
      (node (ref "C2") (pin "1") (pintype "passive"))
      (node (ref "C20") (pin "1") (pintype "passive"))
      (node (ref "C21") (pin "1") (pintype "passive"))
      (node (ref "C22") (pin "1") (pintype "passive"))
      (node (ref "C24") (pin "1") (pintype "passive"))
      (node (ref "C25") (pin "1") (pintype "passive"))
      (node (ref "C3") (pin "1") (pintype "passive"))
      (node (ref "C4") (pin "2") (pintype "passive"))
      (node (ref "C6") (pin "1") (pintype "passive"))
      (node (ref "C7") (pin "1") (pintype "passive"))
      (node (ref "C8") (pin "2") (pintype "passive"))
      (node (ref "C9") (pin "2") (pintype "passive"))
      (node (ref "J1") (pin "100") (pinfunction "100_100") (pintype "passive"))
      (node (ref "J1") (pin "15") (pinfunction "15_15") (pintype "passive"))
      (node (ref "J1") (pin "16") (pinfunction "16_16") (pintype "passive"))
      (node (ref "J1") (pin "21") (pinfunction "21_21") (pintype "passive"))
      (node (ref "J1") (pin "22") (pinfunction "22_22") (pintype "passive"))
      (node (ref "J1") (pin "27") (pinfunction "27_27") (pintype "passive"))
      (node (ref "J1") (pin "28") (pinfunction "28_28") (pintype "passive"))
      (node (ref "J1") (pin "33") (pinfunction "33_33") (pintype "passive"))
      (node (ref "J1") (pin "34") (pinfunction "34_34") (pintype "passive"))
      (node (ref "J1") (pin "39") (pinfunction "39_39") (pintype "passive"))
      (node (ref "J1") (pin "40") (pinfunction "40_40") (pintype "passive"))
      (node (ref "J1") (pin "45") (pinfunction "45_45") (pintype "passive"))
      (node (ref "J1") (pin "46") (pinfunction "46_46") (pintype "passive"))
      (node (ref "J1") (pin "51") (pinfunction "51_51") (pintype "passive"))
      (node (ref "J1") (pin "52") (pinfunction "52_52") (pintype "passive"))
      (node (ref "J1") (pin "65") (pinfunction "65_65") (pintype "passive"))
      (node (ref "J1") (pin "66") (pinfunction "66_66") (pintype "passive"))
      (node (ref "J1") (pin "71") (pinfunction "71_71") (pintype "passive"))
      (node (ref "J1") (pin "72") (pinfunction "72_72") (pintype "passive"))
      (node (ref "J1") (pin "77") (pinfunction "77_77") (pintype "passive"))
      (node (ref "J1") (pin "85") (pinfunction "85_85") (pintype "passive"))
      (node (ref "J1") (pin "86") (pinfunction "86_86") (pintype "passive"))
      (node (ref "J1") (pin "95") (pinfunction "95_95") (pintype "passive"))
      (node (ref "J1") (pin "96") (pinfunction "96_96") (pintype "passive"))
      (node (ref "J1") (pin "97") (pinfunction "97_97") (pintype "passive"))
      (node (ref "J1") (pin "98") (pinfunction "98_98") (pintype "passive"))
      (node (ref "J1") (pin "99") (pinfunction "99_99") (pintype "passive"))
      (node (ref "J12") (pin "0") (pinfunction "Shield_0") (pintype "power_in"))
      (node (ref "J12") (pin "A1") (pinfunction "GND_A1") (pintype "power_in"))
      (node (ref "J12") (pin "A12") (pinfunction "GND_A12") (pintype "power_in"))
      (node (ref "J12") (pin "B1") (pinfunction "GND_B1") (pintype "power_in"))
      (node (ref "J12") (pin "B12") (pinfunction "GND_B12") (pintype "power_in"))
      (node (ref "J16") (pin "1") (pinfunction "1_1") (pintype "passive"))
      (node (ref "J16") (pin "13") (pinfunction "13_13") (pintype "passive"))
      (node (ref "J16") (pin "14") (pinfunction "14_14") (pintype "passive"))
      (node (ref "J16") (pin "2") (pinfunction "2_2") (pintype "passive"))
      (node (ref "J16") (pin "23") (pinfunction "23_23") (pintype "passive"))
      (node (ref "J16") (pin "24") (pinfunction "24_24") (pintype "passive"))
      (node (ref "J16") (pin "29") (pinfunction "29_29") (pintype "passive"))
      (node (ref "J16") (pin "30") (pinfunction "30_30") (pintype "passive"))
      (node (ref "J16") (pin "35") (pinfunction "35_35") (pintype "passive"))
      (node (ref "J16") (pin "36") (pinfunction "36_36") (pintype "passive"))
      (node (ref "J16") (pin "41") (pinfunction "41_41") (pintype "passive"))
      (node (ref "J16") (pin "42") (pinfunction "42_42") (pintype "passive"))
      (node (ref "J16") (pin "47") (pinfunction "47_47") (pintype "passive"))
      (node (ref "J16") (pin "48") (pinfunction "48_48") (pintype "passive"))
      (node (ref "J16") (pin "53") (pinfunction "53_53") (pintype "passive"))
      (node (ref "J16") (pin "54") (pinfunction "54_54") (pintype "passive"))
      (node (ref "J16") (pin "59") (pinfunction "59_59") (pintype "passive"))
      (node (ref "J16") (pin "60") (pinfunction "60_60") (pintype "passive"))
      (node (ref "J16") (pin "69") (pinfunction "69_69") (pintype "passive"))
      (node (ref "J16") (pin "70") (pinfunction "70_70") (pintype "passive"))
      (node (ref "J16") (pin "79") (pinfunction "79_79") (pintype "passive"))
      (node (ref "J16") (pin "80") (pinfunction "80_80") (pintype "passive"))
      (node (ref "J17") (pin "11") (pinfunction "11_11") (pintype "passive"))
      (node (ref "J17") (pin "12") (pinfunction "12_12") (pintype "passive"))
      (node (ref "J17") (pin "21") (pinfunction "21_21") (pintype "passive"))
      (node (ref "J17") (pin "22") (pinfunction "22_22") (pintype "passive"))
      (node (ref "J17") (pin "27") (pinfunction "27_27") (pintype "passive"))
      (node (ref "J17") (pin "28") (pinfunction "28_28") (pintype "passive"))
      (node (ref "J17") (pin "33") (pinfunction "33_33") (pintype "passive"))
      (node (ref "J17") (pin "34") (pinfunction "34_34") (pintype "passive"))
      (node (ref "J17") (pin "39") (pinfunction "39_39") (pintype "passive"))
      (node (ref "J17") (pin "40") (pinfunction "40_40") (pintype "passive"))
      (node (ref "J17") (pin "45") (pinfunction "45_45") (pintype "passive"))
      (node (ref "J17") (pin "46") (pinfunction "46_46") (pintype "passive"))
      (node (ref "J17") (pin "51") (pinfunction "51_51") (pintype "passive"))
      (node (ref "J17") (pin "52") (pinfunction "52_52") (pintype "passive"))
      (node (ref "J17") (pin "57") (pinfunction "57_57") (pintype "passive"))
      (node (ref "J17") (pin "58") (pinfunction "58_58") (pintype "passive"))
      (node (ref "J17") (pin "67") (pinfunction "67_67") (pintype "passive"))
      (node (ref "J17") (pin "68") (pinfunction "68_68") (pintype "passive"))
      (node (ref "J17") (pin "77") (pinfunction "77_77") (pintype "passive"))
      (node (ref "J17") (pin "79") (pinfunction "79_79") (pintype "passive"))
      (node (ref "J17") (pin "80") (pinfunction "80_80") (pintype "passive"))
      (node (ref "J19") (pin "1") (pinfunction "PW_1") (pintype "passive"))
      (node (ref "J2") (pin "15") (pinfunction "15_15") (pintype "passive"))
      (node (ref "J2") (pin "16") (pinfunction "16_16") (pintype "passive"))
      (node (ref "J2") (pin "21") (pinfunction "21_21") (pintype "passive"))
      (node (ref "J2") (pin "22") (pinfunction "22_22") (pintype "passive"))
      (node (ref "J2") (pin "27") (pinfunction "27_27") (pintype "passive"))
      (node (ref "J2") (pin "28") (pinfunction "28_28") (pintype "passive"))
      (node (ref "J2") (pin "33") (pinfunction "33_33") (pintype "passive"))
      (node (ref "J2") (pin "34") (pinfunction "34_34") (pintype "passive"))
      (node (ref "J2") (pin "39") (pinfunction "39_39") (pintype "passive"))
      (node (ref "J2") (pin "40") (pinfunction "40_40") (pintype "passive"))
      (node (ref "J2") (pin "45") (pinfunction "45_45") (pintype "passive"))
      (node (ref "J2") (pin "46") (pinfunction "46_46") (pintype "passive"))
      (node (ref "J2") (pin "51") (pinfunction "51_51") (pintype "passive"))
      (node (ref "J2") (pin "52") (pinfunction "52_52") (pintype "passive"))
      (node (ref "J2") (pin "65") (pinfunction "65_65") (pintype "passive"))
      (node (ref "J2") (pin "66") (pinfunction "66_66") (pintype "passive"))
      (node (ref "J2") (pin "71") (pinfunction "71_71") (pintype "passive"))
      (node (ref "J2") (pin "72") (pinfunction "72_72") (pintype "passive"))
      (node (ref "J2") (pin "77") (pinfunction "77_77") (pintype "passive"))
      (node (ref "J2") (pin "85") (pinfunction "85_85") (pintype "passive"))
      (node (ref "J2") (pin "86") (pinfunction "86_86") (pintype "passive"))
      (node (ref "J2") (pin "91") (pinfunction "91_91") (pintype "passive"))
      (node (ref "J2") (pin "92") (pinfunction "92_92") (pintype "passive"))
      (node (ref "R12") (pin "2") (pinfunction "2_2") (pintype "passive"))
      (node (ref "R16") (pin "2") (pinfunction "2_2") (pintype "passive"))
      (node (ref "R17") (pin "2") (pinfunction "2_2") (pintype "passive"))
      (node (ref "R4") (pin "2") (pinfunction "2_2") (pintype "passive"))
      (node (ref "R8") (pin "1") (pinfunction "1_1") (pintype "passive"))
      (node (ref "U1") (pin "2") (pinfunction "GND_2") (pintype "power_in"))
      (node (ref "U2") (pin "2") (pinfunction "GND_2") (pintype "power_in"))
      (node (ref "U3") (pin "2") (pinfunction "GND_2") (pintype "power_in"))
    )
    (net (code "122") (name "Net-(J3-Pad2)") (class "Default")
      (node (ref "J3") (pin "2") (pinfunction "2_2") (pintype "passive"))
      (node (ref "R1") (pin "1") (pinfunction "1_1") (pintype "passive"))
    )
    (net (code "123") (name "Net-(J4-Pad2)") (class "Default")
      (node (ref "J4") (pin "2") (pinfunction "2_2") (pintype "passive"))
      (node (ref "R2") (pin "1") (pinfunction "1_1") (pintype "passive"))
    )
    (net (code "124") (name "Net-(J5-Pad2)") (class "Default")
      (node (ref "J5") (pin "2") (pinfunction "2_2") (pintype "passive"))
      (node (ref "R3") (pin "1") (pinfunction "1_1") (pintype "passive"))
    )
    (net (code "125") (name "Net-(J6-Pad2)") (class "Default")
      (node (ref "J6") (pin "2") (pinfunction "2_2") (pintype "passive"))
      (node (ref "R5") (pin "2") (pinfunction "2_2") (pintype "passive"))
    )
    (net (code "126") (name "Net-(J7-Pad2)") (class "Default")
      (node (ref "J7") (pin "2") (pinfunction "2_2") (pintype "passive"))
      (node (ref "R6") (pin "2") (pinfunction "2_2") (pintype "passive"))
    )
    (net (code "127") (name "Net-(J8-Pad2)") (class "Default")
      (node (ref "J8") (pin "2") (pinfunction "2_2") (pintype "passive"))
      (node (ref "R7") (pin "2") (pinfunction "2_2") (pintype "passive"))
    )
    (net (code "128") (name "Net-(J9-Pad2)") (class "Default")
      (node (ref "J9") (pin "2") (pinfunction "2_2") (pintype "passive"))
      (node (ref "R9") (pin "1") (pinfunction "1_1") (pintype "passive"))
    )
    (net (code "129") (name "Net-(J10-Pad2)") (class "Default")
      (node (ref "J10") (pin "2") (pinfunction "2_2") (pintype "passive"))
      (node (ref "R10") (pin "1") (pinfunction "1_1") (pintype "passive"))
    )
    (net (code "130") (name "Net-(J11-Pad2)") (class "Default")
      (node (ref "J11") (pin "2") (pinfunction "2_2") (pintype "passive"))
      (node (ref "R11") (pin "1") (pinfunction "1_1") (pintype "passive"))
    )
    (net (code "131") (name "Net-(J12-CC1)") (class "Default")
      (node (ref "J12") (pin "A5") (pinfunction "CC1_A5") (pintype "power_in"))
      (node (ref "R17") (pin "1") (pinfunction "1_1") (pintype "passive"))
    )
    (net (code "132") (name "Net-(J12-CC2)") (class "Default")
      (node (ref "J12") (pin "B5") (pinfunction "CC2_B5") (pintype "power_in"))
      (node (ref "R16") (pin "1") (pinfunction "1_1") (pintype "passive"))
    )
    (net (code "133") (name "Net-(U1-FB)") (class "Default")
      (node (ref "R1") (pin "2") (pinfunction "2_2") (pintype "passive"))
      (node (ref "R2") (pin "2") (pinfunction "2_2") (pintype "passive"))
      (node (ref "R3") (pin "2") (pinfunction "2_2") (pintype "passive"))
      (node (ref "R4") (pin "1") (pinfunction "1_1") (pintype "passive"))
      (node (ref "U1") (pin "5") (pinfunction "FB_5") (pintype "input"))
    )
    (net (code "134") (name "Net-(U1-LX)") (class "Default")
      (node (ref "L1") (pin "1") (pinfunction "1_1") (pintype "passive"))
      (node (ref "U1") (pin "3") (pinfunction "LX_3") (pintype "passive"))
    )
    (net (code "135") (name "Net-(U2-FB)") (class "Default")
      (node (ref "R5") (pin "1") (pinfunction "1_1") (pintype "passive"))
      (node (ref "R6") (pin "1") (pinfunction "1_1") (pintype "passive"))
      (node (ref "R7") (pin "1") (pinfunction "1_1") (pintype "passive"))
      (node (ref "R8") (pin "2") (pinfunction "2_2") (pintype "passive"))
      (node (ref "U2") (pin "5") (pinfunction "FB_5") (pintype "input"))
    )
    (net (code "136") (name "Net-(U2-LX)") (class "Default")
      (node (ref "L2") (pin "1") (pinfunction "1_1") (pintype "passive"))
      (node (ref "U2") (pin "3") (pinfunction "LX_3") (pintype "passive"))
    )
    (net (code "137") (name "Net-(U3-FB)") (class "Default")
      (node (ref "R10") (pin "2") (pinfunction "2_2") (pintype "passive"))
      (node (ref "R11") (pin "2") (pinfunction "2_2") (pintype "passive"))
      (node (ref "R12") (pin "1") (pinfunction "1_1") (pintype "passive"))
      (node (ref "R9") (pin "2") (pinfunction "2_2") (pintype "passive"))
      (node (ref "U3") (pin "5") (pinfunction "FB_5") (pintype "input"))
    )
    (net (code "138") (name "Net-(U3-LX)") (class "Default")
      (node (ref "L3") (pin "1") (pinfunction "1_1") (pintype "passive"))
      (node (ref "U3") (pin "3") (pinfunction "LX_3") (pintype "passive"))
    )
    (net (code "139") (name "VCCIO_13") (class "Default")
      (node (ref "C24") (pin "2") (pintype "passive"))
      (node (ref "C25") (pin "2") (pintype "passive"))
      (node (ref "C7") (pin "2") (pintype "passive"))
      (node (ref "C8") (pin "1") (pintype "passive"))
      (node (ref "J13") (pin "2") (pinfunction "2_2") (pintype "passive"))
      (node (ref "J14") (pin "2") (pinfunction "2_2") (pintype "passive"))
      (node (ref "J2") (pin "98") (pinfunction "98_98") (pintype "passive"))
      (node (ref "J6") (pin "1") (pinfunction "1_1") (pintype "passive"))
      (node (ref "J7") (pin "1") (pinfunction "1_1") (pintype "passive"))
      (node (ref "J8") (pin "1") (pinfunction "1_1") (pintype "passive"))
      (node (ref "L2") (pin "2") (pinfunction "2_2") (pintype "passive"))
    )
    (net (code "140") (name "VCCIO_34") (class "Default")
      (node (ref "C11") (pin "2") (pintype "passive"))
      (node (ref "C12") (pin "1") (pintype "passive"))
      (node (ref "C16") (pin "2") (pintype "passive"))
      (node (ref "C17") (pin "2") (pintype "passive"))
      (node (ref "J1") (pin "78") (pinfunction "78_78") (pintype "passive"))
      (node (ref "J1") (pin "79") (pinfunction "79_79") (pintype "passive"))
      (node (ref "J1") (pin "80") (pinfunction "80_80") (pintype "passive"))
      (node (ref "J10") (pin "1") (pinfunction "1_1") (pintype "passive"))
      (node (ref "J11") (pin "1") (pinfunction "1_1") (pintype "passive"))
      (node (ref "J13") (pin "1") (pinfunction "1_1") (pintype "passive"))
      (node (ref "J15") (pin "1") (pinfunction "1_1") (pintype "passive"))
      (node (ref "J9") (pin "1") (pinfunction "1_1") (pintype "passive"))
      (node (ref "L3") (pin "2") (pinfunction "2_2") (pintype "passive"))
    )
    (net (code "141") (name "VCCIO_35") (class "Default")
      (node (ref "C20") (pin "2") (pintype "passive"))
      (node (ref "C21") (pin "2") (pintype "passive"))
      (node (ref "C22") (pin "2") (pintype "passive"))
      (node (ref "C3") (pin "2") (pintype "passive"))
      (node (ref "C4") (pin "1") (pintype "passive"))
      (node (ref "J14") (pin "1") (pinfunction "1_1") (pintype "passive"))
      (node (ref "J15") (pin "2") (pinfunction "2_2") (pintype "passive"))
      (node (ref "J2") (pin "78") (pinfunction "78_78") (pintype "passive"))
      (node (ref "J2") (pin "79") (pinfunction "79_79") (pintype "passive"))
      (node (ref "J2") (pin "80") (pinfunction "80_80") (pintype "passive"))
      (node (ref "J3") (pin "1") (pinfunction "1_1") (pintype "passive"))
      (node (ref "J4") (pin "1") (pinfunction "1_1") (pintype "passive"))
      (node (ref "J5") (pin "1") (pinfunction "1_1") (pintype "passive"))
      (node (ref "L1") (pin "2") (pinfunction "2_2") (pintype "passive"))
    )
    (net (code "142") (name "unconnected-(J1-Pad1)") (class "Default")
      (node (ref "J1") (pin "1") (pinfunction "1_1") (pintype "passive"))
    )
    (net (code "143") (name "unconnected-(J1-Pad2)") (class "Default")
      (node (ref "J1") (pin "2") (pinfunction "2_2") (pintype "passive"))
    )
    (net (code "144") (name "unconnected-(J1-Pad3)") (class "Default")
      (node (ref "J1") (pin "3") (pinfunction "3_3") (pintype "passive"))
    )
    (net (code "145") (name "unconnected-(J1-Pad4)") (class "Default")
      (node (ref "J1") (pin "4") (pinfunction "4_4") (pintype "passive"))
    )
    (net (code "146") (name "unconnected-(J1-Pad6)") (class "Default")
      (node (ref "J1") (pin "6") (pinfunction "6_6") (pintype "passive"))
    )
    (net (code "147") (name "unconnected-(J1-Pad7)") (class "Default")
      (node (ref "J1") (pin "7") (pinfunction "7_7") (pintype "passive"))
    )
    (net (code "148") (name "unconnected-(J1-Pad8)") (class "Default")
      (node (ref "J1") (pin "8") (pinfunction "8_8") (pintype "passive"))
    )
    (net (code "149") (name "unconnected-(J2-Pad1)") (class "Default")
      (node (ref "J2") (pin "1") (pinfunction "1_1") (pintype "passive"))
    )
    (net (code "150") (name "unconnected-(J2-Pad2)") (class "Default")
      (node (ref "J2") (pin "2") (pinfunction "2_2") (pintype "passive"))
    )
    (net (code "151") (name "unconnected-(J2-Pad3)") (class "Default")
      (node (ref "J2") (pin "3") (pinfunction "3_3") (pintype "passive"))
    )
    (net (code "152") (name "unconnected-(J2-Pad4)") (class "Default")
      (node (ref "J2") (pin "4") (pinfunction "4_4") (pintype "passive"))
    )
    (net (code "153") (name "unconnected-(J2-Pad5)") (class "Default")
      (node (ref "J2") (pin "5") (pinfunction "5_5") (pintype "passive"))
    )
    (net (code "154") (name "unconnected-(J2-Pad6)") (class "Default")
      (node (ref "J2") (pin "6") (pinfunction "6_6") (pintype "passive"))
    )
    (net (code "155") (name "unconnected-(J2-Pad7)") (class "Default")
      (node (ref "J2") (pin "7") (pinfunction "7_7") (pintype "passive"))
    )
    (net (code "156") (name "unconnected-(J2-Pad8)") (class "Default")
      (node (ref "J2") (pin "8") (pinfunction "8_8") (pintype "passive"))
    )
    (net (code "157") (name "unconnected-(J2-Pad9)") (class "Default")
      (node (ref "J2") (pin "9") (pinfunction "9_9") (pintype "passive"))
    )
    (net (code "158") (name "unconnected-(J12-Dn1-PadA7)") (class "Default")
      (node (ref "J12") (pin "A7") (pinfunction "Dn1_A7") (pintype "bidirectional"))
    )
    (net (code "159") (name "unconnected-(J12-Dn2-PadB7)") (class "Default")
      (node (ref "J12") (pin "B7") (pinfunction "Dn2_B7") (pintype "bidirectional"))
    )
    (net (code "160") (name "unconnected-(J12-Dp1-PadA6)") (class "Default")
      (node (ref "J12") (pin "A6") (pinfunction "Dp1_A6") (pintype "bidirectional"))
    )
    (net (code "161") (name "unconnected-(J12-Dp2-PadB6)") (class "Default")
      (node (ref "J12") (pin "B6") (pinfunction "Dp2_B6") (pintype "bidirectional"))
    )
    (net (code "162") (name "unconnected-(J12-SBU1-PadA8)") (class "Default")
      (node (ref "J12") (pin "A8") (pinfunction "SBU1_A8") (pintype "power_in"))
    )
    (net (code "163") (name "unconnected-(J12-SBU2-PadB8)") (class "Default")
      (node (ref "J12") (pin "B8") (pinfunction "SBU2_B8") (pintype "power_in"))
    )
    (net (code "164") (name "unconnected-(J12-SSRXn1-PadB10)") (class "Default")
      (node (ref "J12") (pin "B10") (pinfunction "SSRXn1_B10") (pintype "passive"))
    )
    (net (code "165") (name "unconnected-(J12-SSRXn2-PadA10)") (class "Default")
      (node (ref "J12") (pin "A10") (pinfunction "SSRXn2_A10") (pintype "passive"))
    )
    (net (code "166") (name "unconnected-(J12-SSRXp1-PadB11)") (class "Default")
      (node (ref "J12") (pin "B11") (pinfunction "SSRXp1_B11") (pintype "passive"))
    )
    (net (code "167") (name "unconnected-(J12-SSRXp2-PadA11)") (class "Default")
      (node (ref "J12") (pin "A11") (pinfunction "SSRXp2_A11") (pintype "passive"))
    )
    (net (code "168") (name "unconnected-(J12-SSTXn1-PadA3)") (class "Default")
      (node (ref "J12") (pin "A3") (pinfunction "SSTXn1_A3") (pintype "passive"))
    )
    (net (code "169") (name "unconnected-(J12-SSTXn2-PadB3)") (class "Default")
      (node (ref "J12") (pin "B3") (pinfunction "SSTXn2_B3") (pintype "passive"))
    )
    (net (code "170") (name "unconnected-(J12-SSTXp1-PadA2)") (class "Default")
      (node (ref "J12") (pin "A2") (pinfunction "SSTXp1_A2") (pintype "passive"))
    )
    (net (code "171") (name "unconnected-(J12-SSTXp2-PadB2)") (class "Default")
      (node (ref "J12") (pin "B2") (pinfunction "SSTXp2_B2") (pintype "passive"))
    )
  )
)
